# arduino_final_schematic.net
KiCad netlist of a schematic drawn in EAGLE
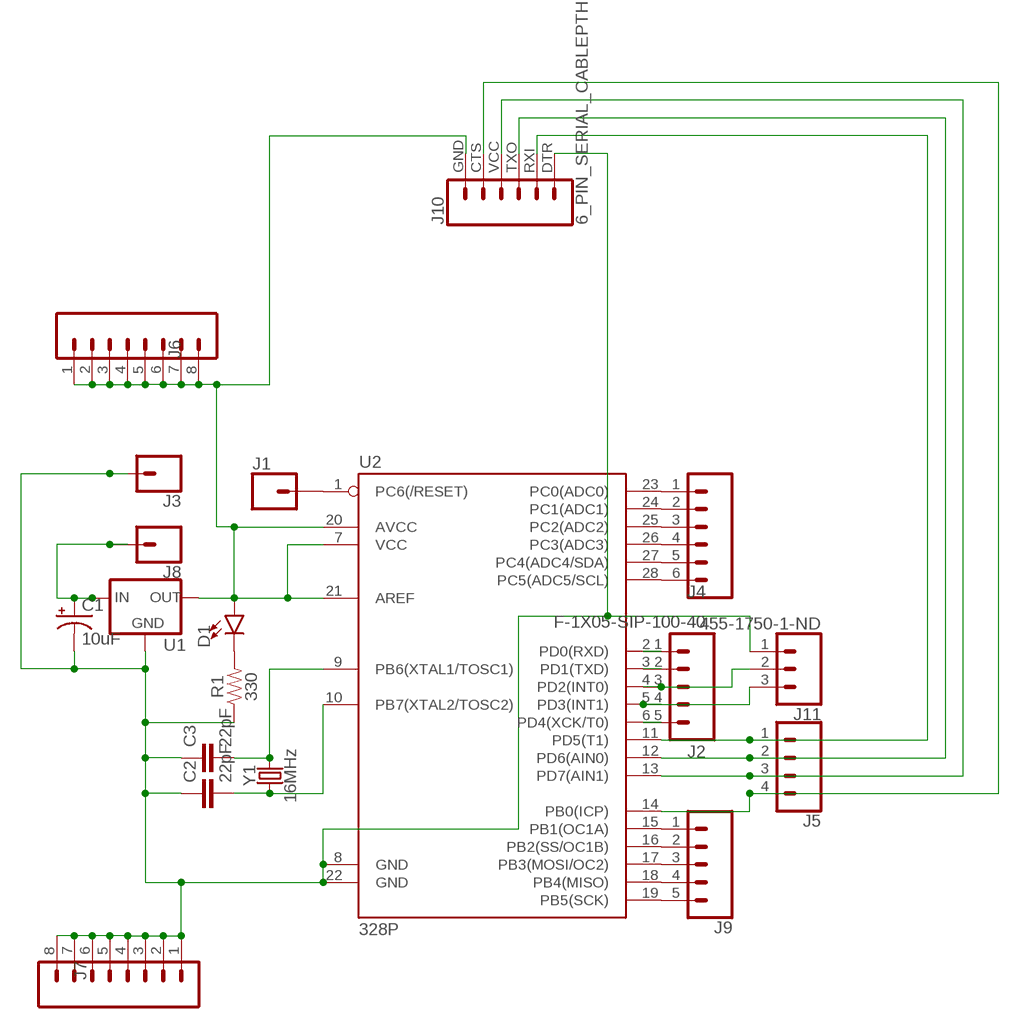
[diagram p0: schematic, sheet 1]

(export (version "E")
  (design (tool "Eeschema 10.0.6"))
  (components
    (comp (ref "C1")
      (value "10uF")
      (footprint "eagle-import:CPOL-RADIAL-2.5MM-5MM")
      (libsource (lib "eagle-import") (part "10UF-POLAR-RADIAL-2.5MM-25V-20%"))
    )
    (comp (ref "C2")
      (value "22pF")
      (footprint "eagle-import:CAP-PTH-2.54")
      (libsource (lib "eagle-import") (part "22PF-PTH-2.54MM-200V-5%"))
    )
    (comp (ref "C3")
      (value "22pF")
      (footprint "eagle-import:CAP-PTH-2.54")
      (libsource (lib "eagle-import") (part "22PF-PTH-2.54MM-200V-5%"))
    )
    (comp (ref "D1")
      (value "LED3MM")
      (footprint "eagle-import:LED_3MM")
      (libsource (lib "eagle-import") (part "LED3MM"))
    )
    (comp (ref "J1")
      (value "CONN_01")
      (footprint "eagle-import:1X01")
      (libsource (lib "eagle-import") (part "CONN_01"))
    )
    (comp (ref "J2")
      (value "F-1X05-SIP-100-40")
      (footprint "eagle-import:1X05")
      (libsource (lib "eagle-import") (part "CONN_05"))
    )
    (comp (ref "J3")
      (value "CONN_01")
      (footprint "eagle-import:1X01")
      (libsource (lib "eagle-import") (part "CONN_01"))
    )
    (comp (ref "J4")
      (value "CONN_06NO_SILK_FEMALE_PTH")
      (footprint "eagle-import:1X06_NO_SILK")
      (libsource (lib "eagle-import") (part "CONN_06NO_SILK_FEMALE_PTH"))
    )
    (comp (ref "J5")
      (value "CONN_04PTH")
      (footprint "eagle-import:1X04")
      (libsource (lib "eagle-import") (part "CONN_04PTH"))
    )
    (comp (ref "J6")
      (value "CONN_08\"")
      (footprint "eagle-import:1X08")
      (libsource (lib "eagle-import") (part "CONN_08{dblquote}"))
    )
    (comp (ref "J7")
      (value "CONN_08\"")
      (footprint "eagle-import:1X08")
      (libsource (lib "eagle-import") (part "CONN_08{dblquote}"))
    )
    (comp (ref "J8")
      (value "CONN_01")
      (footprint "eagle-import:1X01")
      (libsource (lib "eagle-import") (part "CONN_01"))
    )
    (comp (ref "J9")
      (value "CONN_05")
      (footprint "eagle-import:1X05")
      (libsource (lib "eagle-import") (part "CONN_05"))
    )
    (comp (ref "J10")
      (value "6_PIN_SERIAL_CABLEPTH")
      (footprint "eagle-import:FTDI_BASIC")
      (libsource (lib "eagle-import") (part "6_PIN_SERIAL_CABLEPTH"))
    )
    (comp (ref "J11")
      (value "455-1750-1-ND")
      (footprint "eagle-import:1X03")
      (libsource (lib "eagle-import") (part "CONN_03"))
    )
    (comp (ref "R1")
      (value "330")
      (footprint "eagle-import:AXIAL-0.3")
      (libsource (lib "eagle-import") (part "330OHM-HORIZ-1/10W-5%"))
    )
    (comp (ref "U1")
      (value "V_REG_78XX-TO-220")
      (footprint "eagle-import:TO-220-ALT")
      (libsource (lib "eagle-import") (part "V_REG_78XX-TO-220"))
    )
    (comp (ref "U2")
      (value "328P")
      (footprint "eagle-import:DIP28")
      (libsource (lib "eagle-import") (part "ATMEGA328P_PDIP"))
    )
    (comp (ref "Y1")
      (value "16MHz")
      (footprint "eagle-import:HC49US")
      (libsource (lib "eagle-import") (part "CRYSTAL-16MHZPTH-HC49US"))
    )
  )
  (nets
    (net (code "1") (name "Net-(C1-+)") (class "Default")
      (node (ref "C1") (pin "1") (pinfunction "+_1") (pintype "passive"))
      (node (ref "J8") (pin "1") (pinfunction "1_1") (pintype "passive"))
      (node (ref "U1") (pin "IN") (pinfunction "IN_IN") (pintype "input"))
    )
    (net (code "2") (name "Net-(C1--)") (class "Default")
      (node (ref "C1") (pin "2") (pinfunction "-_2") (pintype "passive"))
      (node (ref "C2") (pin "1") (pinfunction "1_1") (pintype "passive"))
      (node (ref "C3") (pin "1") (pinfunction "1_1") (pintype "passive"))
      (node (ref "J10") (pin "DTR") (pinfunction "1_DTR") (pintype "passive"))
      (node (ref "J11") (pin "1") (pinfunction "1_1") (pintype "passive"))
      (node (ref "J3") (pin "1") (pinfunction "1_1") (pintype "passive"))
      (node (ref "J7") (pin "1") (pinfunction "1_1") (pintype "passive"))
      (node (ref "J7") (pin "2") (pinfunction "2_2") (pintype "passive"))
      (node (ref "J7") (pin "3") (pinfunction "3_3") (pintype "passive"))
      (node (ref "J7") (pin "4") (pinfunction "4_4") (pintype "passive"))
      (node (ref "J7") (pin "5") (pinfunction "5_5") (pintype "passive"))
      (node (ref "J7") (pin "6") (pinfunction "6_6") (pintype "passive"))
      (node (ref "J7") (pin "7") (pinfunction "7_7") (pintype "passive"))
      (node (ref "J7") (pin "8") (pinfunction "8_8") (pintype "passive"))
      (node (ref "R1") (pin "P$1") (pinfunction "1_P$1") (pintype "passive"))
      (node (ref "U1") (pin "GND") (pinfunction "GND_GND") (pintype "input"))
      (node (ref "U2") (pin "22") (pinfunction "GND_22") (pintype "bidirectional"))
      (node (ref "U2") (pin "8") (pinfunction "GND_8") (pintype "bidirectional"))
    )
    (net (code "3") (name "Net-(D1-C)") (class "Default")
      (node (ref "D1") (pin "K") (pinfunction "C_K") (pintype "passive"))
      (node (ref "R1") (pin "P$2") (pinfunction "2_P$2") (pintype "passive"))
    )
    (net (code "4") (name "Net-(J10-2)") (class "Default")
      (node (ref "J10") (pin "RXI") (pinfunction "2_RXI") (pintype "passive"))
      (node (ref "J5") (pin "1") (pinfunction "1_1") (pintype "passive"))
      (node (ref "U2") (pin "11") (pinfunction "PD5(T1)_11") (pintype "bidirectional"))
    )
    (net (code "5") (name "Net-(J10-3)") (class "Default")
      (node (ref "J10") (pin "TXO") (pinfunction "3_TXO") (pintype "passive"))
      (node (ref "J5") (pin "2") (pinfunction "2_2") (pintype "passive"))
      (node (ref "U2") (pin "12") (pinfunction "PD6(AIN0)_12") (pintype "bidirectional"))
    )
    (net (code "6") (name "Net-(J10-4)") (class "Default")
      (node (ref "J10") (pin "VCC") (pinfunction "4_VCC") (pintype "passive"))
      (node (ref "J5") (pin "3") (pinfunction "3_3") (pintype "passive"))
      (node (ref "U2") (pin "13") (pinfunction "PD7(AIN1)_13") (pintype "bidirectional"))
    )
    (net (code "7") (name "Net-(J10-5)") (class "Default")
      (node (ref "J10") (pin "CTS") (pinfunction "5_CTS") (pintype "passive"))
      (node (ref "J5") (pin "4") (pinfunction "4_4") (pintype "passive"))
      (node (ref "U2") (pin "14") (pinfunction "PB0(ICP)_14") (pintype "bidirectional"))
    )
    (net (code "8") (name "Net-(J10-6)") (class "Default")
      (node (ref "D1") (pin "A") (pinfunction "A_A") (pintype "passive"))
      (node (ref "J10") (pin "GND") (pinfunction "6_GND") (pintype "passive"))
      (node (ref "J6") (pin "1") (pinfunction "1_1") (pintype "passive"))
      (node (ref "J6") (pin "2") (pinfunction "2_2") (pintype "passive"))
      (node (ref "J6") (pin "3") (pinfunction "3_3") (pintype "passive"))
      (node (ref "J6") (pin "4") (pinfunction "4_4") (pintype "passive"))
      (node (ref "J6") (pin "5") (pinfunction "5_5") (pintype "passive"))
      (node (ref "J6") (pin "6") (pinfunction "6_6") (pintype "passive"))
      (node (ref "J6") (pin "7") (pinfunction "7_7") (pintype "passive"))
      (node (ref "J6") (pin "8") (pinfunction "8_8") (pintype "passive"))
      (node (ref "U1") (pin "OUT") (pinfunction "OUT_OUT") (pintype "passive"))
      (node (ref "U2") (pin "20") (pinfunction "AVCC_20") (pintype "bidirectional"))
      (node (ref "U2") (pin "21") (pinfunction "AREF_21") (pintype "bidirectional"))
      (node (ref "U2") (pin "7") (pinfunction "VCC_7") (pintype "bidirectional"))
    )
    (net (code "9") (name "Net-(U2-PB1(OC1A))") (class "Default")
      (node (ref "J9") (pin "1") (pinfunction "1_1") (pintype "passive"))
      (node (ref "U2") (pin "15") (pinfunction "PB1(OC1A)_15") (pintype "bidirectional"))
    )
    (net (code "10") (name "Net-(U2-PB2(SS{slash}OC1B))") (class "Default")
      (node (ref "J9") (pin "2") (pinfunction "2_2") (pintype "passive"))
      (node (ref "U2") (pin "16") (pinfunction "PB2(SS/OC1B)_16") (pintype "bidirectional"))
    )
    (net (code "11") (name "Net-(U2-PB3(MOSI{slash}OC2))") (class "Default")
      (node (ref "J9") (pin "3") (pinfunction "3_3") (pintype "passive"))
      (node (ref "U2") (pin "17") (pinfunction "PB3(MOSI/OC2)_17") (pintype "bidirectional"))
    )
    (net (code "12") (name "Net-(U2-PB4(MISO))") (class "Default")
      (node (ref "J9") (pin "4") (pinfunction "4_4") (pintype "passive"))
      (node (ref "U2") (pin "18") (pinfunction "PB4(MISO)_18") (pintype "bidirectional"))
    )
    (net (code "13") (name "Net-(U2-PB5(SCK))") (class "Default")
      (node (ref "J9") (pin "5") (pinfunction "5_5") (pintype "passive"))
      (node (ref "U2") (pin "19") (pinfunction "PB5(SCK)_19") (pintype "bidirectional"))
    )
    (net (code "14") (name "Net-(U2-PB6(XTAL1{slash}TOSC1))") (class "Default")
      (node (ref "C3") (pin "2") (pinfunction "2_2") (pintype "passive"))
      (node (ref "U2") (pin "9") (pinfunction "PB6(XTAL1/TOSC1)_9") (pintype "bidirectional"))
      (node (ref "Y1") (pin "2") (pinfunction "2_2") (pintype "passive"))
    )
    (net (code "15") (name "Net-(U2-PB7(XTAL2{slash}TOSC2))") (class "Default")
      (node (ref "C2") (pin "2") (pinfunction "2_2") (pintype "passive"))
      (node (ref "U2") (pin "10") (pinfunction "PB7(XTAL2/TOSC2)_10") (pintype "bidirectional"))
      (node (ref "Y1") (pin "1") (pinfunction "1_1") (pintype "passive"))
    )
    (net (code "16") (name "Net-(U2-PC0(ADC0))") (class "Default")
      (node (ref "J4") (pin "1") (pinfunction "1_1") (pintype "passive"))
      (node (ref "U2") (pin "23") (pinfunction "PC0(ADC0)_23") (pintype "bidirectional"))
    )
    (net (code "17") (name "Net-(U2-PC1(ADC1))") (class "Default")
      (node (ref "J4") (pin "2") (pinfunction "2_2") (pintype "passive"))
      (node (ref "U2") (pin "24") (pinfunction "PC1(ADC1)_24") (pintype "bidirectional"))
    )
    (net (code "18") (name "Net-(U2-PC2(ADC2))") (class "Default")
      (node (ref "J4") (pin "3") (pinfunction "3_3") (pintype "passive"))
      (node (ref "U2") (pin "25") (pinfunction "PC2(ADC2)_25") (pintype "bidirectional"))
    )
    (net (code "19") (name "Net-(U2-PC3(ADC3))") (class "Default")
      (node (ref "J4") (pin "4") (pinfunction "4_4") (pintype "passive"))
      (node (ref "U2") (pin "26") (pinfunction "PC3(ADC3)_26") (pintype "bidirectional"))
    )
    (net (code "20") (name "Net-(U2-PC4(ADC4{slash}SDA))") (class "Default")
      (node (ref "J4") (pin "5") (pinfunction "5_5") (pintype "passive"))
      (node (ref "U2") (pin "27") (pinfunction "PC4(ADC4/SDA)_27") (pintype "bidirectional"))
    )
    (net (code "21") (name "Net-(U2-PC5(ADC5{slash}SCL))") (class "Default")
      (node (ref "J4") (pin "6") (pinfunction "6_6") (pintype "passive"))
      (node (ref "U2") (pin "28") (pinfunction "PC5(ADC5/SCL)_28") (pintype "bidirectional"))
    )
    (net (code "22") (name "Net-(U2-PC6({slash}RESET))") (class "Default")
      (node (ref "J1") (pin "1") (pinfunction "1_1") (pintype "passive"))
      (node (ref "U2") (pin "1") (pinfunction "PC6(/RESET)_1") (pintype "bidirectional"))
    )
    (net (code "23") (name "Net-(U2-PD0(RXD))") (class "Default")
      (node (ref "J2") (pin "1") (pinfunction "1_1") (pintype "passive"))
      (node (ref "U2") (pin "2") (pinfunction "PD0(RXD)_2") (pintype "bidirectional"))
    )
    (net (code "24") (name "Net-(U2-PD1(TXD))") (class "Default")
      (node (ref "J2") (pin "2") (pinfunction "2_2") (pintype "passive"))
      (node (ref "U2") (pin "3") (pinfunction "PD1(TXD)_3") (pintype "bidirectional"))
    )
    (net (code "25") (name "Net-(U2-PD2(INT0))") (class "Default")
      (node (ref "J11") (pin "2") (pinfunction "2_2") (pintype "passive"))
      (node (ref "J2") (pin "3") (pinfunction "3_3") (pintype "passive"))
      (node (ref "U2") (pin "4") (pinfunction "PD2(INT0)_4") (pintype "bidirectional"))
    )
    (net (code "26") (name "Net-(U2-PD3(INT1))") (class "Default")
      (node (ref "J11") (pin "3") (pinfunction "3_3") (pintype "passive"))
      (node (ref "J2") (pin "4") (pinfunction "4_4") (pintype "passive"))
      (node (ref "U2") (pin "5") (pinfunction "PD3(INT1)_5") (pintype "bidirectional"))
    )
    (net (code "27") (name "Net-(U2-PD4(XCK{slash}T0))") (class "Default")
      (node (ref "J2") (pin "5") (pinfunction "5_5") (pintype "passive"))
      (node (ref "U2") (pin "6") (pinfunction "PD4(XCK/T0)_6") (pintype "bidirectional"))
    )
  )
)
